# Power.net
KiCad netlist of a schematic drawn in Altium Designer
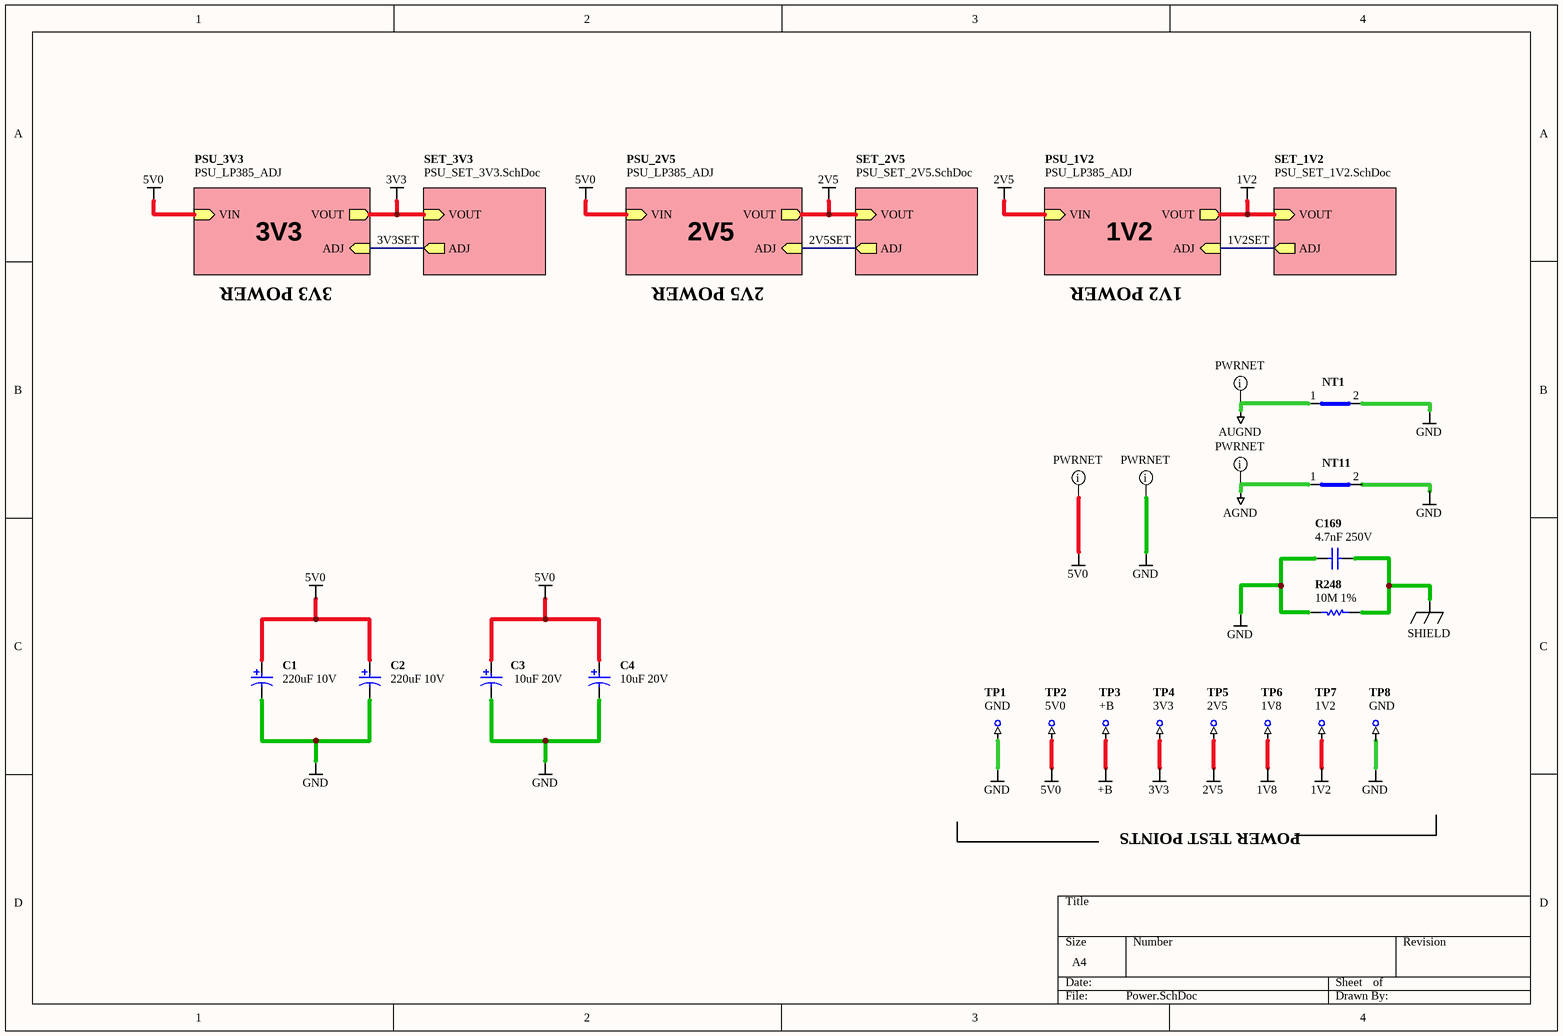
[diagram p0: Power.SchDoc]

(export (version "E")
  (design (tool "Eeschema 10.0.6"))
  (components
    (comp (ref "C1")
      (value "220uF 10V")
      (footprint "CAPC7343-STAR")
      (description "Capacitor, Tantalum, 220uF 10% 10V MCCT-D (7343-31)")
      (fields (field (name "TOLERANCE") "10 %"))
      (libsource (lib "altium-import") (part "root_0_CAP-P_"))
    )
    (comp (ref "C2")
      (value "220uF 10V")
      (footprint "CAPC7343-STAR")
      (description "Capacitor, Tantalum, 220uF 10% 10V MCCT-D (7343-31)")
      (fields (field (name "TOLERANCE") "10 %"))
      (libsource (lib "altium-import") (part "root_0_CAP-P_"))
    )
    (comp (ref "C3")
      (value "10uF 20V")
      (footprint "CAPC3528-STAR")
      (description "Capacitor, Tantalum, 10uF 10% 20V MCCT-B (3528)")
      (fields (field (name "TOLERANCE") "10 %"))
      (libsource (lib "altium-import") (part "root_0_CAP-P_"))
    )
    (comp (ref "C4")
      (value "10uF 20V")
      (footprint "CAPC3528-STAR")
      (description "Capacitor, Tantalum, 10uF 10% 20V MCCT-B (3528)")
      (fields (field (name "TOLERANCE") "10 %"))
      (libsource (lib "altium-import") (part "root_0_CAP-P_"))
    )
    (comp (ref "C169")
      (value "4.7nF 250V")
      (footprint "CAPM7163")
      (description "Capacitor, Ceramic, 4.7nF 20% 250V Panasonic BC J Lead (CAPM7163) Y5V")
      (fields (field (name "TOLERANCE") "20% %"))
      (libsource (lib "AltiumDesignLibrary") (part "CAP-NP"))
    )
    (comp (ref "NT1")
      (value "Net Tie SMT2")
      (footprint "NETTIE-SMT2-31X39")
      (description "Net-Tie, Surface Mount, 2 x 2.0mm x 0.8mm SMT Pads - For 0.8mm Track")
      (libsource (lib "AltiumDesignLibrary") (part "NETTIE-SMT2"))
    )
    (comp (ref "NT11")
      (value "Net Tie SMT2")
      (footprint "NETTIE-SMT2-8X8")
      (description "Net-Tie, Surface Mount, 2 x 2.0mm x 0.8mm SMT Pads - For 0.8mm Track")
      (libsource (lib "AltiumDesignLibrary") (part "NETTIE-SMT2"))
    )
    (comp (ref "R248")
      (value "10M 1%")
      (footprint "RESC3216")
      (description "Resistor, 10M 1%1206 (3216)")
      (fields (field (name "TOLERANCE") "1 %"))
      (libsource (lib "AltiumDesignLibrary") (part "RES"))
    )
    (comp (ref "TP1")
      (value "GND")
      (footprint "TestPin")
      (description "Test Point, PCB Mount with Silkscreen Box")
      (libsource (lib "AltiumDesignLibrary") (part "TestPin"))
    )
    (comp (ref "TP2")
      (value "5V0")
      (footprint "TestPin")
      (description "Test Point, PCB Mount with Silkscreen Box")
      (libsource (lib "AltiumDesignLibrary") (part "TestPin"))
    )
    (comp (ref "TP3")
      (value "+B")
      (footprint "TestPin")
      (description "Test Point, PCB Mount with Silkscreen Box")
      (libsource (lib "AltiumDesignLibrary") (part "TestPin"))
    )
    (comp (ref "TP4")
      (value "3V3")
      (footprint "TestPin")
      (description "Test Point, PCB Mount with Silkscreen Box")
      (libsource (lib "AltiumDesignLibrary") (part "TestPin"))
    )
    (comp (ref "TP5")
      (value "2V5")
      (footprint "TestPin")
      (description "Test Point, PCB Mount with Silkscreen Box")
      (libsource (lib "AltiumDesignLibrary") (part "TestPin"))
    )
    (comp (ref "TP6")
      (value "1V8")
      (footprint "TestPin")
      (description "Test Point, PCB Mount with Silkscreen Box")
      (libsource (lib "AltiumDesignLibrary") (part "TestPin"))
    )
    (comp (ref "TP7")
      (value "1V2")
      (footprint "TestPin")
      (description "Test Point, PCB Mount with Silkscreen Box")
      (libsource (lib "AltiumDesignLibrary") (part "TestPin"))
    )
    (comp (ref "TP8")
      (value "GND")
      (footprint "TestPin")
      (description "Test Point, PCB Mount with Silkscreen Box")
      (libsource (lib "AltiumDesignLibrary") (part "TestPin"))
    )
  )
  (nets
    (net (code "1") (name "+B") (class "Default")
      (node (ref "TP3") (pin "1") (pinfunction "1_1") (pintype "input"))
    )
    (net (code "5") (name "1V2") (class "Default")
      (node (ref "TP7") (pin "1") (pinfunction "1_1") (pintype "input"))
    )
    (net (code "6") (name "1V8") (class "Default")
      (node (ref "TP6") (pin "1") (pinfunction "1_1") (pintype "input"))
    )
    (net (code "7") (name "2V5") (class "Default")
      (node (ref "TP5") (pin "1") (pinfunction "1_1") (pintype "input"))
    )
    (net (code "8") (name "3V3") (class "Default")
      (node (ref "TP4") (pin "1") (pinfunction "1_1") (pintype "input"))
    )
    (net (code "9") (name "5V0") (class "Default")
      (node (ref "C1") (pin "1") (pinfunction "1_1") (pintype "passive"))
      (node (ref "C2") (pin "1") (pinfunction "1_1") (pintype "passive"))
      (node (ref "C3") (pin "1") (pinfunction "1_1") (pintype "passive"))
      (node (ref "C4") (pin "1") (pinfunction "1_1") (pintype "passive"))
      (node (ref "TP2") (pin "1") (pinfunction "1_1") (pintype "input"))
    )
    (net (code "10") (name "AGND") (class "Default")
      (node (ref "NT11") (pin "1") (pinfunction "Net1_1") (pintype "passive"))
    )
    (net (code "11") (name "AUGND") (class "Default")
      (node (ref "NT1") (pin "1") (pinfunction "Net1_1") (pintype "passive"))
    )
    (net (code "12") (name "GND") (class "Default")
      (node (ref "C1") (pin "2") (pinfunction "2_2") (pintype "passive"))
      (node (ref "C169") (pin "2") (pinfunction "2_2") (pintype "passive"))
      (node (ref "C2") (pin "2") (pinfunction "2_2") (pintype "passive"))
      (node (ref "C3") (pin "2") (pinfunction "2_2") (pintype "passive"))
      (node (ref "C4") (pin "2") (pinfunction "2_2") (pintype "passive"))
      (node (ref "NT1") (pin "2") (pinfunction "Net2_2") (pintype "passive"))
      (node (ref "NT11") (pin "2") (pinfunction "Net2_2") (pintype "passive"))
      (node (ref "R248") (pin "2") (pinfunction "2_2") (pintype "passive"))
      (node (ref "TP1") (pin "1") (pinfunction "1_1") (pintype "input"))
      (node (ref "TP8") (pin "1") (pinfunction "1_1") (pintype "input"))
    )
    (net (code "13") (name "SHIELD") (class "Default")
      (node (ref "C169") (pin "1") (pinfunction "1_1") (pintype "passive"))
      (node (ref "R248") (pin "1") (pinfunction "1_1") (pintype "passive"))
    )
  )
)
